# 4x3keyboard.net
KiCad netlist of a schematic drawn in EAGLE
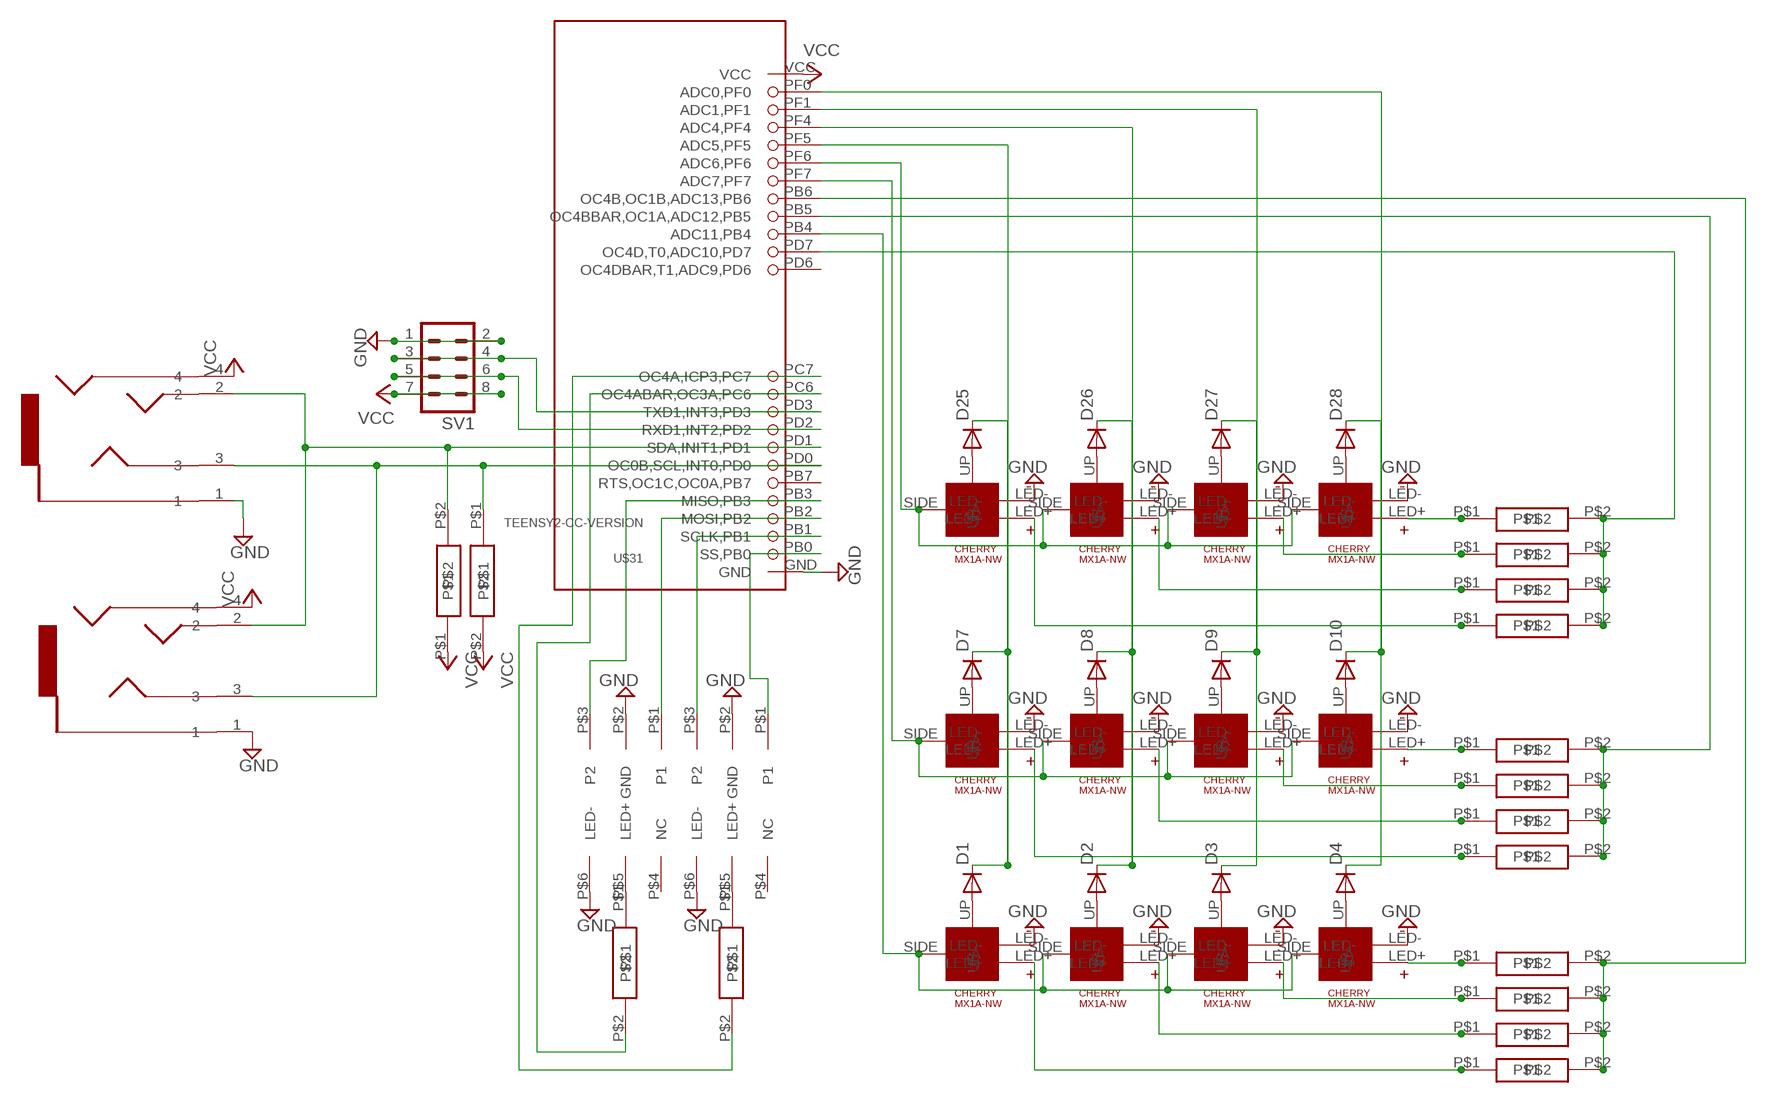
[diagram p0: schematic, sheet 1]

(export (version "E")
  (design (tool "Eeschema 10.0.6"))
  (components
    (comp (ref "COMM")
      (value "SJ-43514_HEADPHONES_3.5MM_X4")
      (footprint "eagle-import:SJ-43514_HEADPHONES-3.5MM_X4")
      (libsource (lib "eagle-import") (part "SJ-43514_HEADPHONES_3.5MM_X4"))
    )
    (comp (ref "COMM1")
      (value "SJ-43514_HEADPHONES_3.5MM_X4")
      (footprint "eagle-import:SJ-43514_HEADPHONES-3.5MM_X4")
      (libsource (lib "eagle-import") (part "SJ-43514_HEADPHONES_3.5MM_X4"))
    )
    (comp (ref "D1")
      (value "1N4148DO35-7")
      (footprint "eagle-import:DO35-7")
      (libsource (lib "eagle-import") (part "1N4148DO35-7"))
    )
    (comp (ref "D2")
      (value "1N4148DO35-7")
      (footprint "eagle-import:DO35-7")
      (libsource (lib "eagle-import") (part "1N4148DO35-7"))
    )
    (comp (ref "D3")
      (value "1N4148DO35-7")
      (footprint "eagle-import:DO35-7")
      (libsource (lib "eagle-import") (part "1N4148DO35-7"))
    )
    (comp (ref "D4")
      (value "1N4148DO35-7")
      (footprint "eagle-import:DO35-7")
      (libsource (lib "eagle-import") (part "1N4148DO35-7"))
    )
    (comp (ref "D7")
      (value "1N4148DO35-7")
      (footprint "eagle-import:DO35-7")
      (libsource (lib "eagle-import") (part "1N4148DO35-7"))
    )
    (comp (ref "D8")
      (value "1N4148DO35-7")
      (footprint "eagle-import:DO35-7")
      (libsource (lib "eagle-import") (part "1N4148DO35-7"))
    )
    (comp (ref "D9")
      (value "1N4148DO35-7")
      (footprint "eagle-import:DO35-7")
      (libsource (lib "eagle-import") (part "1N4148DO35-7"))
    )
    (comp (ref "D10")
      (value "1N4148DO35-7")
      (footprint "eagle-import:DO35-7")
      (libsource (lib "eagle-import") (part "1N4148DO35-7"))
    )
    (comp (ref "D25")
      (value "1N4148DO35-7")
      (footprint "eagle-import:DO35-7")
      (libsource (lib "eagle-import") (part "1N4148DO35-7"))
    )
    (comp (ref "D26")
      (value "1N4148DO35-7")
      (footprint "eagle-import:DO35-7")
      (libsource (lib "eagle-import") (part "1N4148DO35-7"))
    )
    (comp (ref "D27")
      (value "1N4148DO35-7")
      (footprint "eagle-import:DO35-7")
      (libsource (lib "eagle-import") (part "1N4148DO35-7"))
    )
    (comp (ref "D28")
      (value "1N4148DO35-7")
      (footprint "eagle-import:DO35-7")
      (libsource (lib "eagle-import") (part "1N4148DO35-7"))
    )
    (comp (ref "SV1")
      (value "MA04-2")
      (footprint "eagle-import:MA04-2")
      (libsource (lib "eagle-import") (part "MA04-2"))
    )
    (comp (ref "U$1")
      (value "CHERRY-MX1A-E1NW-LED")
      (footprint "eagle-import:CHERRYMX-NN-LED")
      (libsource (lib "eagle-import") (part "CHERRY-MX1A-E1NW-LED"))
    )
    (comp (ref "U$2")
      (value "CHERRY-MX1A-E1NW-LED")
      (footprint "eagle-import:CHERRYMX-NN-LED")
      (libsource (lib "eagle-import") (part "CHERRY-MX1A-E1NW-LED"))
    )
    (comp (ref "U$3")
      (value "CHERRY-MX1A-E1NW-LED")
      (footprint "eagle-import:CHERRYMX-NN-LED")
      (libsource (lib "eagle-import") (part "CHERRY-MX1A-E1NW-LED"))
    )
    (comp (ref "U$4")
      (value "CHERRY-MX1A-E1NW-LED")
      (footprint "eagle-import:CHERRYMX-NN-LED")
      (libsource (lib "eagle-import") (part "CHERRY-MX1A-E1NW-LED"))
    )
    (comp (ref "U$5")
      (value "RESISTORBIGPAD")
      (footprint "eagle-import:RESISTORBIGPAD")
      (libsource (lib "eagle-import") (part "RESISTORBIGPAD"))
    )
    (comp (ref "U$6")
      (value "RESISTORBIGPAD")
      (footprint "eagle-import:RESISTORBIGPAD")
      (libsource (lib "eagle-import") (part "RESISTORBIGPAD"))
    )
    (comp (ref "U$7")
      (value "CHERRY-MX1A-E1NW-LED")
      (footprint "eagle-import:CHERRYMX-NN-LED")
      (libsource (lib "eagle-import") (part "CHERRY-MX1A-E1NW-LED"))
    )
    (comp (ref "U$8")
      (value "CHERRY-MX1A-E1NW-LED")
      (footprint "eagle-import:CHERRYMX-NN-LED")
      (libsource (lib "eagle-import") (part "CHERRY-MX1A-E1NW-LED"))
    )
    (comp (ref "U$9")
      (value "CHERRY-MX1A-E1NW-LED")
      (footprint "eagle-import:CHERRYMX-NN-LED")
      (libsource (lib "eagle-import") (part "CHERRY-MX1A-E1NW-LED"))
    )
    (comp (ref "U$10")
      (value "CHERRY-MX1A-E1NW-LED")
      (footprint "eagle-import:CHERRYMX-NN-LED")
      (libsource (lib "eagle-import") (part "CHERRY-MX1A-E1NW-LED"))
    )
    (comp (ref "U$11")
      (value "RESISTORBIGPAD")
      (footprint "eagle-import:RESISTORBIGPAD")
      (libsource (lib "eagle-import") (part "RESISTORBIGPAD"))
    )
    (comp (ref "U$12")
      (value "RESISTORBIGPAD")
      (footprint "eagle-import:RESISTORBIGPAD")
      (libsource (lib "eagle-import") (part "RESISTORBIGPAD"))
    )
    (comp (ref "U$13")
      (value "RESISTORBIGPAD")
      (footprint "eagle-import:RESISTORBIGPAD")
      (libsource (lib "eagle-import") (part "RESISTORBIGPAD"))
    )
    (comp (ref "U$14")
      (value "RESISTORBIGPAD")
      (footprint "eagle-import:RESISTORBIGPAD")
      (libsource (lib "eagle-import") (part "RESISTORBIGPAD"))
    )
    (comp (ref "U$15")
      (value "RESISTORBIGPAD")
      (footprint "eagle-import:RESISTORBIGPAD")
      (libsource (lib "eagle-import") (part "RESISTORBIGPAD"))
    )
    (comp (ref "U$16")
      (value "RESISTORBIGPAD")
      (footprint "eagle-import:RESISTORBIGPAD")
      (libsource (lib "eagle-import") (part "RESISTORBIGPAD"))
    )
    (comp (ref "U$17")
      (value "RESISTORBIGPAD")
      (footprint "eagle-import:RESISTORBIGPAD")
      (libsource (lib "eagle-import") (part "RESISTORBIGPAD"))
    )
    (comp (ref "U$18")
      (value "RESISTORBIGPAD")
      (footprint "eagle-import:RESISTORBIGPAD")
      (libsource (lib "eagle-import") (part "RESISTORBIGPAD"))
    )
    (comp (ref "U$19")
      (value "RESISTORBIGPAD")
      (footprint "eagle-import:RESISTORBIGPAD")
      (libsource (lib "eagle-import") (part "RESISTORBIGPAD"))
    )
    (comp (ref "U$20")
      (value "RESISTORBIGPAD")
      (footprint "eagle-import:RESISTORBIGPAD")
      (libsource (lib "eagle-import") (part "RESISTORBIGPAD"))
    )
    (comp (ref "U$21")
      (value "RESISTORBIGPAD")
      (footprint "eagle-import:RESISTORBIGPAD")
      (libsource (lib "eagle-import") (part "RESISTORBIGPAD"))
    )
    (comp (ref "U$22")
      (value "RESISTORBIGPAD")
      (footprint "eagle-import:RESISTORBIGPAD")
      (libsource (lib "eagle-import") (part "RESISTORBIGPAD"))
    )
    (comp (ref "U$23")
      (value "NKK_GW_SERIES")
      (footprint "eagle-import:NKK_GW_SERIES")
      (libsource (lib "eagle-import") (part "NKK_GW_SERIES"))
    )
    (comp (ref "U$24")
      (value "NKK_GW_SERIES")
      (footprint "eagle-import:NKK_GW_SERIES")
      (libsource (lib "eagle-import") (part "NKK_GW_SERIES"))
    )
    (comp (ref "U$25")
      (value "CHERRY-MX1A-E1NW-LED")
      (footprint "eagle-import:CHERRYMX-NN-LED")
      (libsource (lib "eagle-import") (part "CHERRY-MX1A-E1NW-LED"))
    )
    (comp (ref "U$26")
      (value "CHERRY-MX1A-E1NW-LED")
      (footprint "eagle-import:CHERRYMX-NN-LED")
      (libsource (lib "eagle-import") (part "CHERRY-MX1A-E1NW-LED"))
    )
    (comp (ref "U$27")
      (value "CHERRY-MX1A-E1NW-LED")
      (footprint "eagle-import:CHERRYMX-NN-LED")
      (libsource (lib "eagle-import") (part "CHERRY-MX1A-E1NW-LED"))
    )
    (comp (ref "U$28")
      (value "CHERRY-MX1A-E1NW-LED")
      (footprint "eagle-import:CHERRYMX-NN-LED")
      (libsource (lib "eagle-import") (part "CHERRY-MX1A-E1NW-LED"))
    )
    (comp (ref "U$29")
      (value "RESISTORBIGPAD")
      (footprint "eagle-import:RESISTORBIGPAD")
      (libsource (lib "eagle-import") (part "RESISTORBIGPAD"))
    )
    (comp (ref "U$30")
      (value "RESISTORBIGPAD")
      (footprint "eagle-import:RESISTORBIGPAD")
      (libsource (lib "eagle-import") (part "RESISTORBIGPAD"))
    )
    (comp (ref "U$31")
      (value "TEENSY2-CC-VERSION")
      (footprint "eagle-import:TEENSY2")
      (libsource (lib "eagle-import") (part "TEENSY2-CC-VERSION"))
    )
  )
  (nets
    (net (code "1") (name "GND") (class "Default")
      (node (ref "COMM") (pin "1") (pinfunction "1_1") (pintype "bidirectional"))
      (node (ref "COMM1") (pin "1") (pinfunction "1_1") (pintype "bidirectional"))
      (node (ref "SV1") (pin "1") (pinfunction "1_1") (pintype "passive"))
      (node (ref "SV1") (pin "2") (pinfunction "2_2") (pintype "passive"))
      (node (ref "U$1") (pin "LED-") (pinfunction "LED-_LED-") (pintype "bidirectional"))
      (node (ref "U$10") (pin "LED-") (pinfunction "LED-_LED-") (pintype "bidirectional"))
      (node (ref "U$2") (pin "LED-") (pinfunction "LED-_LED-") (pintype "bidirectional"))
      (node (ref "U$23") (pin "P$2") (pinfunction "GND_P$2") (pintype "bidirectional"))
      (node (ref "U$23") (pin "P$6") (pinfunction "LED-_P$6") (pintype "bidirectional"))
      (node (ref "U$24") (pin "P$2") (pinfunction "GND_P$2") (pintype "bidirectional"))
      (node (ref "U$24") (pin "P$6") (pinfunction "LED-_P$6") (pintype "bidirectional"))
      (node (ref "U$25") (pin "LED-") (pinfunction "LED-_LED-") (pintype "bidirectional"))
      (node (ref "U$26") (pin "LED-") (pinfunction "LED-_LED-") (pintype "bidirectional"))
      (node (ref "U$27") (pin "LED-") (pinfunction "LED-_LED-") (pintype "bidirectional"))
      (node (ref "U$28") (pin "LED-") (pinfunction "LED-_LED-") (pintype "bidirectional"))
      (node (ref "U$3") (pin "LED-") (pinfunction "LED-_LED-") (pintype "bidirectional"))
      (node (ref "U$31") (pin "GND") (pinfunction "GND_GND") (pintype "power_in"))
      (node (ref "U$4") (pin "LED-") (pinfunction "LED-_LED-") (pintype "bidirectional"))
      (node (ref "U$7") (pin "LED-") (pinfunction "LED-_LED-") (pintype "bidirectional"))
      (node (ref "U$8") (pin "LED-") (pinfunction "LED-_LED-") (pintype "bidirectional"))
      (node (ref "U$9") (pin "LED-") (pinfunction "LED-_LED-") (pintype "bidirectional"))
    )
    (net (code "2") (name "Net-(D1-PadA)") (class "Default")
      (node (ref "D1") (pin "A") (pinfunction "A_A") (pintype "passive"))
      (node (ref "U$2") (pin "UP") (pinfunction "UP_UP") (pintype "bidirectional"))
    )
    (net (code "3") (name "Net-(D2-PadA)") (class "Default")
      (node (ref "D2") (pin "A") (pinfunction "A_A") (pintype "passive"))
      (node (ref "U$1") (pin "UP") (pinfunction "UP_UP") (pintype "bidirectional"))
    )
    (net (code "4") (name "Net-(D3-PadA)") (class "Default")
      (node (ref "D3") (pin "A") (pinfunction "A_A") (pintype "passive"))
      (node (ref "U$3") (pin "UP") (pinfunction "UP_UP") (pintype "bidirectional"))
    )
    (net (code "5") (name "Net-(D4-PadA)") (class "Default")
      (node (ref "D4") (pin "A") (pinfunction "A_A") (pintype "passive"))
      (node (ref "U$4") (pin "UP") (pinfunction "UP_UP") (pintype "bidirectional"))
    )
    (net (code "6") (name "Net-(D7-PadA)") (class "Default")
      (node (ref "D7") (pin "A") (pinfunction "A_A") (pintype "passive"))
      (node (ref "U$7") (pin "UP") (pinfunction "UP_UP") (pintype "bidirectional"))
    )
    (net (code "7") (name "Net-(D8-PadA)") (class "Default")
      (node (ref "D8") (pin "A") (pinfunction "A_A") (pintype "passive"))
      (node (ref "U$8") (pin "UP") (pinfunction "UP_UP") (pintype "bidirectional"))
    )
    (net (code "8") (name "Net-(D9-PadA)") (class "Default")
      (node (ref "D9") (pin "A") (pinfunction "A_A") (pintype "passive"))
      (node (ref "U$9") (pin "UP") (pinfunction "UP_UP") (pintype "bidirectional"))
    )
    (net (code "9") (name "Net-(D10-PadA)") (class "Default")
      (node (ref "D10") (pin "A") (pinfunction "A_A") (pintype "passive"))
      (node (ref "U$10") (pin "UP") (pinfunction "UP_UP") (pintype "bidirectional"))
    )
    (net (code "10") (name "Net-(D25-PadA)") (class "Default")
      (node (ref "D25") (pin "A") (pinfunction "A_A") (pintype "passive"))
      (node (ref "U$25") (pin "UP") (pinfunction "UP_UP") (pintype "bidirectional"))
    )
    (net (code "11") (name "Net-(D26-PadA)") (class "Default")
      (node (ref "D26") (pin "A") (pinfunction "A_A") (pintype "passive"))
      (node (ref "U$26") (pin "UP") (pinfunction "UP_UP") (pintype "bidirectional"))
    )
    (net (code "12") (name "Net-(D27-PadA)") (class "Default")
      (node (ref "D27") (pin "A") (pinfunction "A_A") (pintype "passive"))
      (node (ref "U$27") (pin "UP") (pinfunction "UP_UP") (pintype "bidirectional"))
    )
    (net (code "13") (name "Net-(D28-PadA)") (class "Default")
      (node (ref "D28") (pin "A") (pinfunction "A_A") (pintype "passive"))
      (node (ref "U$28") (pin "UP") (pinfunction "UP_UP") (pintype "bidirectional"))
    )
    (net (code "14") (name "Net-(U$1-A)") (class "Default")
      (node (ref "U$1") (pin "SIDE") (pinfunction "A_SIDE") (pintype "bidirectional"))
      (node (ref "U$2") (pin "SIDE") (pinfunction "A_SIDE") (pintype "bidirectional"))
      (node (ref "U$3") (pin "SIDE") (pinfunction "A_SIDE") (pintype "bidirectional"))
      (node (ref "U$31") (pin "PB4") (pinfunction "ADC11,PB4_PB4") (pintype "bidirectional"))
      (node (ref "U$4") (pin "SIDE") (pinfunction "A_SIDE") (pintype "bidirectional"))
    )
    (net (code "15") (name "Net-(U$1-PadLED+)") (class "Default")
      (node (ref "U$1") (pin "LED+") (pinfunction "LED+_LED+") (pintype "bidirectional"))
      (node (ref "U$6") (pin "P$1") (pinfunction "P$1_P$1") (pintype "bidirectional"))
    )
    (net (code "16") (name "Net-(U$2-PadLED+)") (class "Default")
      (node (ref "U$2") (pin "LED+") (pinfunction "LED+_LED+") (pintype "bidirectional"))
      (node (ref "U$5") (pin "P$1") (pinfunction "P$1_P$1") (pintype "bidirectional"))
    )
    (net (code "17") (name "Net-(U$10-A)") (class "Default")
      (node (ref "U$10") (pin "SIDE") (pinfunction "A_SIDE") (pintype "bidirectional"))
      (node (ref "U$31") (pin "PF7") (pinfunction "ADC7,PF7_PF7") (pintype "bidirectional"))
      (node (ref "U$7") (pin "SIDE") (pinfunction "A_SIDE") (pintype "bidirectional"))
      (node (ref "U$8") (pin "SIDE") (pinfunction "A_SIDE") (pintype "bidirectional"))
      (node (ref "U$9") (pin "SIDE") (pinfunction "A_SIDE") (pintype "bidirectional"))
    )
    (net (code "18") (name "Net-(U$10-PadLED+)") (class "Default")
      (node (ref "U$10") (pin "LED+") (pinfunction "LED+_LED+") (pintype "bidirectional"))
      (node (ref "U$13") (pin "P$1") (pinfunction "P$1_P$1") (pintype "bidirectional"))
    )
    (net (code "19") (name "Net-(U$11-PadP$1)") (class "Default")
      (node (ref "U$11") (pin "P$1") (pinfunction "P$1_P$1") (pintype "bidirectional"))
      (node (ref "U$3") (pin "LED+") (pinfunction "LED+_LED+") (pintype "bidirectional"))
    )
    (net (code "20") (name "Net-(U$12-PadP$1)") (class "Default")
      (node (ref "U$12") (pin "P$1") (pinfunction "P$1_P$1") (pintype "bidirectional"))
      (node (ref "U$4") (pin "LED+") (pinfunction "LED+_LED+") (pintype "bidirectional"))
    )
    (net (code "21") (name "Net-(U$14-PadP$1)") (class "Default")
      (node (ref "U$14") (pin "P$1") (pinfunction "P$1_P$1") (pintype "bidirectional"))
      (node (ref "U$9") (pin "LED+") (pinfunction "LED+_LED+") (pintype "bidirectional"))
    )
    (net (code "22") (name "Net-(U$15-PadP$1)") (class "Default")
      (node (ref "U$15") (pin "P$1") (pinfunction "P$1_P$1") (pintype "bidirectional"))
      (node (ref "U$8") (pin "LED+") (pinfunction "LED+_LED+") (pintype "bidirectional"))
    )
    (net (code "23") (name "Net-(U$16-PadP$1)") (class "Default")
      (node (ref "U$16") (pin "P$1") (pinfunction "P$1_P$1") (pintype "bidirectional"))
      (node (ref "U$7") (pin "LED+") (pinfunction "LED+_LED+") (pintype "bidirectional"))
    )
    (net (code "24") (name "Net-(U$17-PadP$1)") (class "Default")
      (node (ref "U$17") (pin "P$1") (pinfunction "P$1_P$1") (pintype "bidirectional"))
      (node (ref "U$28") (pin "LED+") (pinfunction "LED+_LED+") (pintype "bidirectional"))
    )
    (net (code "25") (name "Net-(U$18-PadP$1)") (class "Default")
      (node (ref "U$18") (pin "P$1") (pinfunction "P$1_P$1") (pintype "bidirectional"))
      (node (ref "U$27") (pin "LED+") (pinfunction "LED+_LED+") (pintype "bidirectional"))
    )
    (net (code "26") (name "Net-(U$19-PadP$1)") (class "Default")
      (node (ref "U$19") (pin "P$1") (pinfunction "P$1_P$1") (pintype "bidirectional"))
      (node (ref "U$26") (pin "LED+") (pinfunction "LED+_LED+") (pintype "bidirectional"))
    )
    (net (code "27") (name "Net-(U$20-PadP$1)") (class "Default")
      (node (ref "U$20") (pin "P$1") (pinfunction "P$1_P$1") (pintype "bidirectional"))
      (node (ref "U$25") (pin "LED+") (pinfunction "LED+_LED+") (pintype "bidirectional"))
    )
    (net (code "28") (name "Net-(U$23-LED+)") (class "Default")
      (node (ref "U$23") (pin "P$5") (pinfunction "LED+_P$5") (pintype "bidirectional"))
      (node (ref "U$29") (pin "P$1") (pinfunction "P$1_P$1") (pintype "bidirectional"))
    )
    (net (code "29") (name "Net-(U$23-P1)") (class "Default")
      (node (ref "U$23") (pin "P$1") (pinfunction "P1_P$1") (pintype "bidirectional"))
      (node (ref "U$31") (pin "PB2") (pinfunction "MOSI,PB2_PB2") (pintype "bidirectional"))
    )
    (net (code "30") (name "Net-(U$23-P2)") (class "Default")
      (node (ref "U$23") (pin "P$3") (pinfunction "P2_P$3") (pintype "bidirectional"))
      (node (ref "U$31") (pin "PB3") (pinfunction "MISO,PB3_PB3") (pintype "bidirectional"))
    )
    (net (code "31") (name "Net-(U$24-LED+)") (class "Default")
      (node (ref "U$24") (pin "P$5") (pinfunction "LED+_P$5") (pintype "bidirectional"))
      (node (ref "U$30") (pin "P$1") (pinfunction "P$1_P$1") (pintype "bidirectional"))
    )
    (net (code "32") (name "Net-(U$24-P1)") (class "Default")
      (node (ref "U$24") (pin "P$1") (pinfunction "P1_P$1") (pintype "bidirectional"))
      (node (ref "U$31") (pin "PB0") (pinfunction "SS,PB0_PB0") (pintype "bidirectional"))
    )
    (net (code "33") (name "Net-(U$24-P2)") (class "Default")
      (node (ref "U$24") (pin "P$3") (pinfunction "P2_P$3") (pintype "bidirectional"))
      (node (ref "U$31") (pin "PB1") (pinfunction "SCLK,PB1_PB1") (pintype "bidirectional"))
    )
    (net (code "34") (name "Net-(U$25-A)") (class "Default")
      (node (ref "U$25") (pin "SIDE") (pinfunction "A_SIDE") (pintype "bidirectional"))
      (node (ref "U$26") (pin "SIDE") (pinfunction "A_SIDE") (pintype "bidirectional"))
      (node (ref "U$27") (pin "SIDE") (pinfunction "A_SIDE") (pintype "bidirectional"))
      (node (ref "U$28") (pin "SIDE") (pinfunction "A_SIDE") (pintype "bidirectional"))
      (node (ref "U$31") (pin "PF6") (pinfunction "ADC6,PF6_PF6") (pintype "bidirectional"))
    )
    (net (code "35") (name "Net-(U$31-ADC0,PF0)") (class "Default")
      (node (ref "D10") (pin "C") (pinfunction "C_C") (pintype "passive"))
      (node (ref "D28") (pin "C") (pinfunction "C_C") (pintype "passive"))
      (node (ref "D4") (pin "C") (pinfunction "C_C") (pintype "passive"))
      (node (ref "U$31") (pin "PF0") (pinfunction "ADC0,PF0_PF0") (pintype "bidirectional"))
    )
    (net (code "36") (name "Net-(U$31-ADC1,PF1)") (class "Default")
      (node (ref "D27") (pin "C") (pinfunction "C_C") (pintype "passive"))
      (node (ref "D3") (pin "C") (pinfunction "C_C") (pintype "passive"))
      (node (ref "D9") (pin "C") (pinfunction "C_C") (pintype "passive"))
      (node (ref "U$31") (pin "PF1") (pinfunction "ADC1,PF1_PF1") (pintype "bidirectional"))
    )
    (net (code "37") (name "Net-(U$31-ADC4,PF4)") (class "Default")
      (node (ref "D2") (pin "C") (pinfunction "C_C") (pintype "passive"))
      (node (ref "D26") (pin "C") (pinfunction "C_C") (pintype "passive"))
      (node (ref "D8") (pin "C") (pinfunction "C_C") (pintype "passive"))
      (node (ref "U$31") (pin "PF4") (pinfunction "ADC4,PF4_PF4") (pintype "bidirectional"))
    )
    (net (code "38") (name "Net-(U$31-ADC5,PF5)") (class "Default")
      (node (ref "D1") (pin "C") (pinfunction "C_C") (pintype "passive"))
      (node (ref "D25") (pin "C") (pinfunction "C_C") (pintype "passive"))
      (node (ref "D7") (pin "C") (pinfunction "C_C") (pintype "passive"))
      (node (ref "U$31") (pin "PF5") (pinfunction "ADC5,PF5_PF5") (pintype "bidirectional"))
    )
    (net (code "39") (name "Net-(U$31-OC0B,SCL,INT0,PD0)") (class "Default")
      (node (ref "COMM") (pin "3") (pinfunction "3_3") (pintype "bidirectional"))
      (node (ref "COMM1") (pin "3") (pinfunction "3_3") (pintype "bidirectional"))
      (node (ref "U$22") (pin "P$1") (pinfunction "P$1_P$1") (pintype "bidirectional"))
      (node (ref "U$31") (pin "PD0") (pinfunction "OC0B,SCL,INT0,PD0_PD0") (pintype "bidirectional"))
    )
    (net (code "40") (name "Net-(U$31-OC4A,ICP3,PC7)") (class "Default")
      (node (ref "U$30") (pin "P$2") (pinfunction "P$2_P$2") (pintype "bidirectional"))
      (node (ref "U$31") (pin "PC7") (pinfunction "OC4A,ICP3,PC7_PC7") (pintype "bidirectional"))
    )
    (net (code "41") (name "Net-(U$31-OC4ABAR,OC3A,PC6)") (class "Default")
      (node (ref "U$29") (pin "P$2") (pinfunction "P$2_P$2") (pintype "bidirectional"))
      (node (ref "U$31") (pin "PC6") (pinfunction "OC4ABAR,OC3A,PC6_PC6") (pintype "bidirectional"))
    )
    (net (code "42") (name "Net-(U$31-OC4B,OC1B,ADC13,PB6)") (class "Default")
      (node (ref "U$11") (pin "P$2") (pinfunction "P$2_P$2") (pintype "bidirectional"))
      (node (ref "U$12") (pin "P$2") (pinfunction "P$2_P$2") (pintype "bidirectional"))
      (node (ref "U$31") (pin "PB6") (pinfunction "OC4B,OC1B,ADC13,PB6_PB6") (pintype "bidirectional"))
      (node (ref "U$5") (pin "P$2") (pinfunction "P$2_P$2") (pintype "bidirectional"))
      (node (ref "U$6") (pin "P$2") (pinfunction "P$2_P$2") (pintype "bidirectional"))
    )
    (net (code "43") (name "Net-(U$31-OC4BBAR,OC1A,ADC12,PB5)") (class "Default")
      (node (ref "U$13") (pin "P$2") (pinfunction "P$2_P$2") (pintype "bidirectional"))
      (node (ref "U$14") (pin "P$2") (pinfunction "P$2_P$2") (pintype "bidirectional"))
      (node (ref "U$15") (pin "P$2") (pinfunction "P$2_P$2") (pintype "bidirectional"))
      (node (ref "U$16") (pin "P$2") (pinfunction "P$2_P$2") (pintype "bidirectional"))
      (node (ref "U$31") (pin "PB5") (pinfunction "OC4BBAR,OC1A,ADC12,PB5_PB5") (pintype "bidirectional"))
    )
    (net (code "44") (name "Net-(U$31-OC4D,T0,ADC10,PD7)") (class "Default")
      (node (ref "U$17") (pin "P$2") (pinfunction "P$2_P$2") (pintype "bidirectional"))
      (node (ref "U$18") (pin "P$2") (pinfunction "P$2_P$2") (pintype "bidirectional"))
      (node (ref "U$19") (pin "P$2") (pinfunction "P$2_P$2") (pintype "bidirectional"))
      (node (ref "U$20") (pin "P$2") (pinfunction "P$2_P$2") (pintype "bidirectional"))
      (node (ref "U$31") (pin "PD7") (pinfunction "OC4D,T0,ADC10,PD7_PD7") (pintype "bidirectional"))
    )
    (net (code "45") (name "Net-(U$31-RXD1,INT2,PD2)") (class "Default")
      (node (ref "SV1") (pin "5") (pinfunction "5_5") (pintype "passive"))
      (node (ref "SV1") (pin "6") (pinfunction "6_6") (pintype "passive"))
      (node (ref "U$31") (pin "PD2") (pinfunction "RXD1,INT2,PD2_PD2") (pintype "bidirectional"))
    )
    (net (code "46") (name "Net-(U$31-SDA,INIT1,PD1)") (class "Default")
      (node (ref "COMM") (pin "2") (pinfunction "2_2") (pintype "bidirectional"))
      (node (ref "COMM1") (pin "2") (pinfunction "2_2") (pintype "bidirectional"))
      (node (ref "U$21") (pin "P$2") (pinfunction "P$2_P$2") (pintype "bidirectional"))
      (node (ref "U$31") (pin "PD1") (pinfunction "SDA,INIT1,PD1_PD1") (pintype "bidirectional"))
    )
    (net (code "47") (name "Net-(U$31-TXD1,INT3,PD3)") (class "Default")
      (node (ref "SV1") (pin "3") (pinfunction "3_3") (pintype "passive"))
      (node (ref "SV1") (pin "4") (pinfunction "4_4") (pintype "passive"))
      (node (ref "U$31") (pin "PD3") (pinfunction "TXD1,INT3,PD3_PD3") (pintype "bidirectional"))
    )
    (net (code "48") (name "VCC") (class "Default")
      (node (ref "COMM") (pin "4") (pinfunction "4_4") (pintype "bidirectional"))
      (node (ref "COMM1") (pin "4") (pinfunction "4_4") (pintype "bidirectional"))
      (node (ref "SV1") (pin "7") (pinfunction "7_7") (pintype "passive"))
      (node (ref "SV1") (pin "8") (pinfunction "8_8") (pintype "passive"))
      (node (ref "U$21") (pin "P$1") (pinfunction "P$1_P$1") (pintype "bidirectional"))
      (node (ref "U$22") (pin "P$2") (pinfunction "P$2_P$2") (pintype "bidirectional"))
      (node (ref "U$31") (pin "VCC") (pinfunction "VCC_VCC") (pintype "power_in"))
    )
    (net (code "49") (name "unconnected-(U$23-NC-PadP$4)") (class "Default")
      (node (ref "U$23") (pin "P$4") (pinfunction "NC_P$4") (pintype "bidirectional"))
    )
    (net (code "50") (name "unconnected-(U$24-NC-PadP$4)") (class "Default")
      (node (ref "U$24") (pin "P$4") (pinfunction "NC_P$4") (pintype "bidirectional"))
    )
    (net (code "51") (name "unconnected-(U$31-OC4DBAR,T1,ADC9,PD6-PadPD6)") (class "Default")
      (node (ref "U$31") (pin "PD6") (pinfunction "OC4DBAR,T1,ADC9,PD6_PD6") (pintype "bidirectional"))
    )
    (net (code "52") (name "unconnected-(U$31-RTS,OC1C,OC0A,PB7-PadPB7)") (class "Default")
      (node (ref "U$31") (pin "PB7") (pinfunction "RTS,OC1C,OC0A,PB7_PB7") (pintype "bidirectional"))
    )
  )
)
